# MoBoxLader.net
KiCad netlist of a schematic drawn in EAGLE
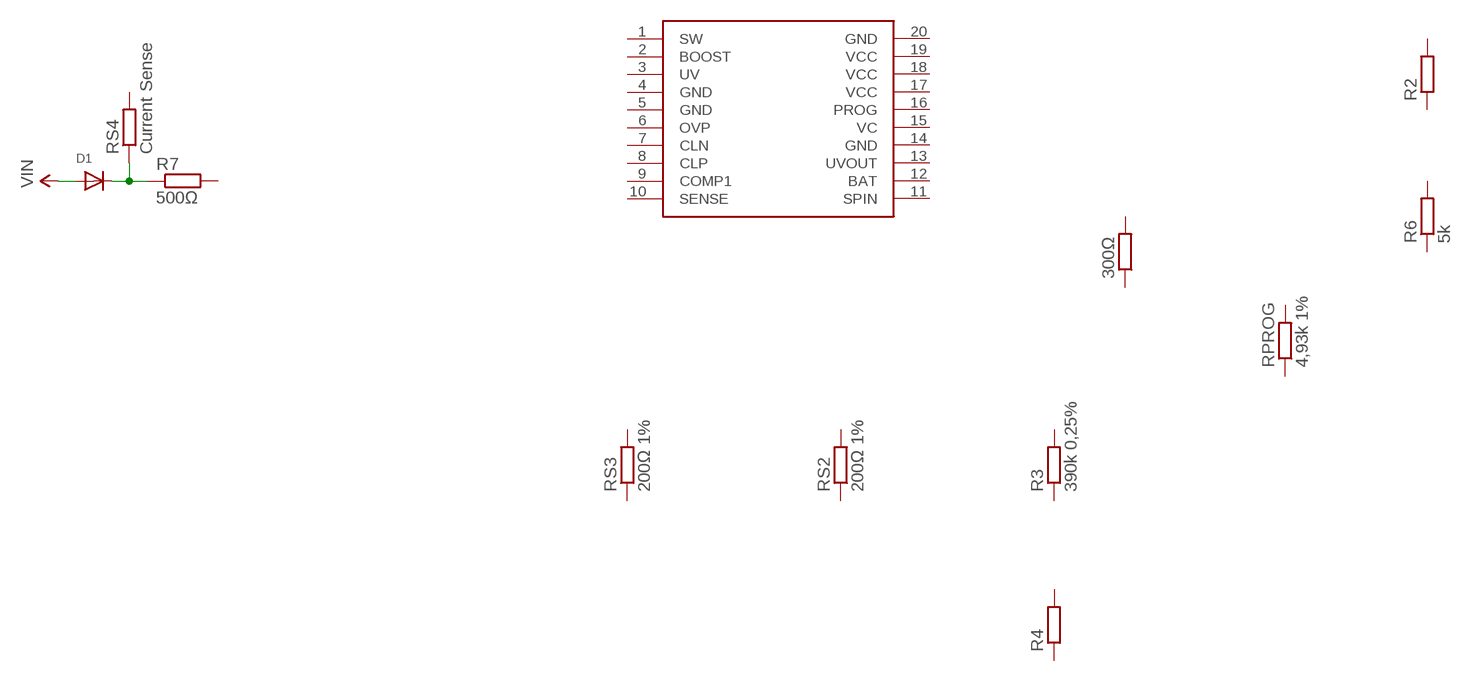
[diagram p0: schematic, sheet 1]

(export (version "E")
  (design (tool "Eeschema 10.0.6"))
  (components
    (comp (ref "300Ω")
      (value "R-EU_M0805")
      (footprint "eagle-import:M0805")
      (libsource (lib "eagle-import") (part "R-EU_M0805"))
    )
    (comp (ref "D1")
      (value "DIODESMA")
      (footprint "eagle-import:SMADIODE")
      (libsource (lib "eagle-import") (part "DIODESMA"))
    )
    (comp (ref "R2")
      (value "R-EU_M0805")
      (footprint "eagle-import:M0805")
      (libsource (lib "eagle-import") (part "R-EU_M0805"))
    )
    (comp (ref "R3")
      (value "390k 0,25%")
      (footprint "eagle-import:M0805")
      (libsource (lib "eagle-import") (part "R-EU_M0805"))
    )
    (comp (ref "R4")
      (value "R-EU_M0805")
      (footprint "eagle-import:M0805")
      (libsource (lib "eagle-import") (part "R-EU_M0805"))
    )
    (comp (ref "R6")
      (value "5k")
      (footprint "eagle-import:M0805")
      (libsource (lib "eagle-import") (part "R-EU_M0805"))
    )
    (comp (ref "R7")
      (value "500Ω")
      (footprint "eagle-import:M0805")
      (libsource (lib "eagle-import") (part "R-EU_M0805"))
    )
    (comp (ref "RPROG")
      (value "4,93k 1%")
      (footprint "eagle-import:M0805")
      (libsource (lib "eagle-import") (part "R-EU_M0805"))
    )
    (comp (ref "RS2")
      (value "200Ω 1%")
      (footprint "eagle-import:M0805")
      (libsource (lib "eagle-import") (part "R-EU_M0805"))
    )
    (comp (ref "RS3")
      (value "200Ω 1%")
      (footprint "eagle-import:M0805")
      (libsource (lib "eagle-import") (part "R-EU_M0805"))
    )
    (comp (ref "RS4")
      (value "Current Sense")
      (footprint "eagle-import:M0805")
      (libsource (lib "eagle-import") (part "R-EU_M0805"))
    )
    (comp (ref "U$1")
      (value "LT1769")
      (footprint "eagle-import:TSSOP24")
      (libsource (lib "eagle-import") (part "LT1769"))
    )
  )
  (nets
    (net (code "1") (name "Net-(D1-PadC)") (class "Default")
      (node (ref "D1") (pin "C") (pinfunction "C_C") (pintype "passive"))
      (node (ref "R7") (pin "1") (pinfunction "1_1") (pintype "passive"))
      (node (ref "RS4") (pin "1") (pinfunction "1_1") (pintype "passive"))
    )
    (net (code "2") (name "VIN") (class "Default")
      (node (ref "D1") (pin "A") (pinfunction "A_A") (pintype "passive"))
    )
    (net (code "3") (name "unconnected-(300Ω-Pad1)") (class "Default")
      (node (ref "300Ω") (pin "1") (pinfunction "1_1") (pintype "passive"))
    )
    (net (code "4") (name "unconnected-(300Ω-Pad2)") (class "Default")
      (node (ref "300Ω") (pin "2") (pinfunction "2_2") (pintype "passive"))
    )
    (net (code "5") (name "unconnected-(R2-Pad1)") (class "Default")
      (node (ref "R2") (pin "1") (pinfunction "1_1") (pintype "passive"))
    )
    (net (code "6") (name "unconnected-(R2-Pad2)") (class "Default")
      (node (ref "R2") (pin "2") (pinfunction "2_2") (pintype "passive"))
    )
    (net (code "7") (name "unconnected-(R3-Pad1)") (class "Default")
      (node (ref "R3") (pin "1") (pinfunction "1_1") (pintype "passive"))
    )
    (net (code "8") (name "unconnected-(R3-Pad2)") (class "Default")
      (node (ref "R3") (pin "2") (pinfunction "2_2") (pintype "passive"))
    )
    (net (code "9") (name "unconnected-(R4-Pad1)") (class "Default")
      (node (ref "R4") (pin "1") (pinfunction "1_1") (pintype "passive"))
    )
    (net (code "10") (name "unconnected-(R4-Pad2)") (class "Default")
      (node (ref "R4") (pin "2") (pinfunction "2_2") (pintype "passive"))
    )
    (net (code "11") (name "unconnected-(R6-Pad1)") (class "Default")
      (node (ref "R6") (pin "1") (pinfunction "1_1") (pintype "passive"))
    )
    (net (code "12") (name "unconnected-(R6-Pad2)") (class "Default")
      (node (ref "R6") (pin "2") (pinfunction "2_2") (pintype "passive"))
    )
    (net (code "13") (name "unconnected-(R7-Pad2)") (class "Default")
      (node (ref "R7") (pin "2") (pinfunction "2_2") (pintype "passive"))
    )
    (net (code "14") (name "unconnected-(RPROG-Pad1)") (class "Default")
      (node (ref "RPROG") (pin "1") (pinfunction "1_1") (pintype "passive"))
    )
    (net (code "15") (name "unconnected-(RPROG-Pad2)") (class "Default")
      (node (ref "RPROG") (pin "2") (pinfunction "2_2") (pintype "passive"))
    )
    (net (code "16") (name "unconnected-(RS2-Pad1)") (class "Default")
      (node (ref "RS2") (pin "1") (pinfunction "1_1") (pintype "passive"))
    )
    (net (code "17") (name "unconnected-(RS2-Pad2)") (class "Default")
      (node (ref "RS2") (pin "2") (pinfunction "2_2") (pintype "passive"))
    )
    (net (code "18") (name "unconnected-(RS3-Pad1)") (class "Default")
      (node (ref "RS3") (pin "1") (pinfunction "1_1") (pintype "passive"))
    )
    (net (code "19") (name "unconnected-(RS3-Pad2)") (class "Default")
      (node (ref "RS3") (pin "2") (pinfunction "2_2") (pintype "passive"))
    )
    (net (code "20") (name "unconnected-(RS4-Pad2)") (class "Default")
      (node (ref "RS4") (pin "2") (pinfunction "2_2") (pintype "passive"))
    )
    (net (code "21") (name "unconnected-(U$1-BAT-Pad12)") (class "Default")
      (node (ref "U$1") (pin "12") (pinfunction "BAT_12") (pintype "bidirectional"))
    )
    (net (code "22") (name "unconnected-(U$1-BOOST-Pad2)") (class "Default")
      (node (ref "U$1") (pin "2") (pinfunction "BOOST_2") (pintype "bidirectional"))
    )
    (net (code "23") (name "unconnected-(U$1-CLN-Pad7)") (class "Default")
      (node (ref "U$1") (pin "7") (pinfunction "CLN_7") (pintype "bidirectional"))
    )
    (net (code "24") (name "unconnected-(U$1-CLP-Pad8)") (class "Default")
      (node (ref "U$1") (pin "8") (pinfunction "CLP_8") (pintype "bidirectional"))
    )
    (net (code "25") (name "unconnected-(U$1-COMP1-Pad9)") (class "Default")
      (node (ref "U$1") (pin "9") (pinfunction "COMP1_9") (pintype "bidirectional"))
    )
    (net (code "26") (name "unconnected-(U$1-GND-Pad4)") (class "Default")
      (node (ref "U$1") (pin "4") (pinfunction "GND_4") (pintype "bidirectional"))
    )
    (net (code "27") (name "unconnected-(U$1-GND-Pad5)") (class "Default")
      (node (ref "U$1") (pin "5") (pinfunction "GND_5") (pintype "bidirectional"))
    )
    (net (code "28") (name "unconnected-(U$1-GND-Pad14)") (class "Default")
      (node (ref "U$1") (pin "14") (pinfunction "GND_14") (pintype "bidirectional"))
    )
    (net (code "29") (name "unconnected-(U$1-GND-Pad20)") (class "Default")
      (node (ref "U$1") (pin "20") (pinfunction "GND_20") (pintype "bidirectional"))
    )
    (net (code "30") (name "unconnected-(U$1-OVP-Pad6)") (class "Default")
      (node (ref "U$1") (pin "6") (pinfunction "OVP_6") (pintype "bidirectional"))
    )
    (net (code "31") (name "unconnected-(U$1-PROG-Pad16)") (class "Default")
      (node (ref "U$1") (pin "16") (pinfunction "PROG_16") (pintype "bidirectional"))
    )
    (net (code "32") (name "unconnected-(U$1-SENSE-Pad10)") (class "Default")
      (node (ref "U$1") (pin "10") (pinfunction "SENSE_10") (pintype "bidirectional"))
    )
    (net (code "33") (name "unconnected-(U$1-SPIN-Pad11)") (class "Default")
      (node (ref "U$1") (pin "11") (pinfunction "SPIN_11") (pintype "bidirectional"))
    )
    (net (code "34") (name "unconnected-(U$1-SW-Pad1)") (class "Default")
      (node (ref "U$1") (pin "1") (pinfunction "SW_1") (pintype "bidirectional"))
    )
    (net (code "35") (name "unconnected-(U$1-UV-Pad3)") (class "Default")
      (node (ref "U$1") (pin "3") (pinfunction "UV_3") (pintype "bidirectional"))
    )
    (net (code "36") (name "unconnected-(U$1-UVOUT-Pad13)") (class "Default")
      (node (ref "U$1") (pin "13") (pinfunction "UVOUT_13") (pintype "bidirectional"))
    )
    (net (code "37") (name "unconnected-(U$1-VC-Pad15)") (class "Default")
      (node (ref "U$1") (pin "15") (pinfunction "VC_15") (pintype "bidirectional"))
    )
    (net (code "38") (name "unconnected-(U$1-VCC-Pad17)") (class "Default")
      (node (ref "U$1") (pin "17") (pinfunction "VCC_17") (pintype "bidirectional"))
    )
    (net (code "39") (name "unconnected-(U$1-VCC-Pad18)") (class "Default")
      (node (ref "U$1") (pin "18") (pinfunction "VCC_18") (pintype "bidirectional"))
    )
    (net (code "40") (name "unconnected-(U$1-VCC-Pad19)") (class "Default")
      (node (ref "U$1") (pin "19") (pinfunction "VCC_19") (pintype "bidirectional"))
    )
  )
)
